# M633X.net
KiCad netlist of a schematic drawn in EAGLE
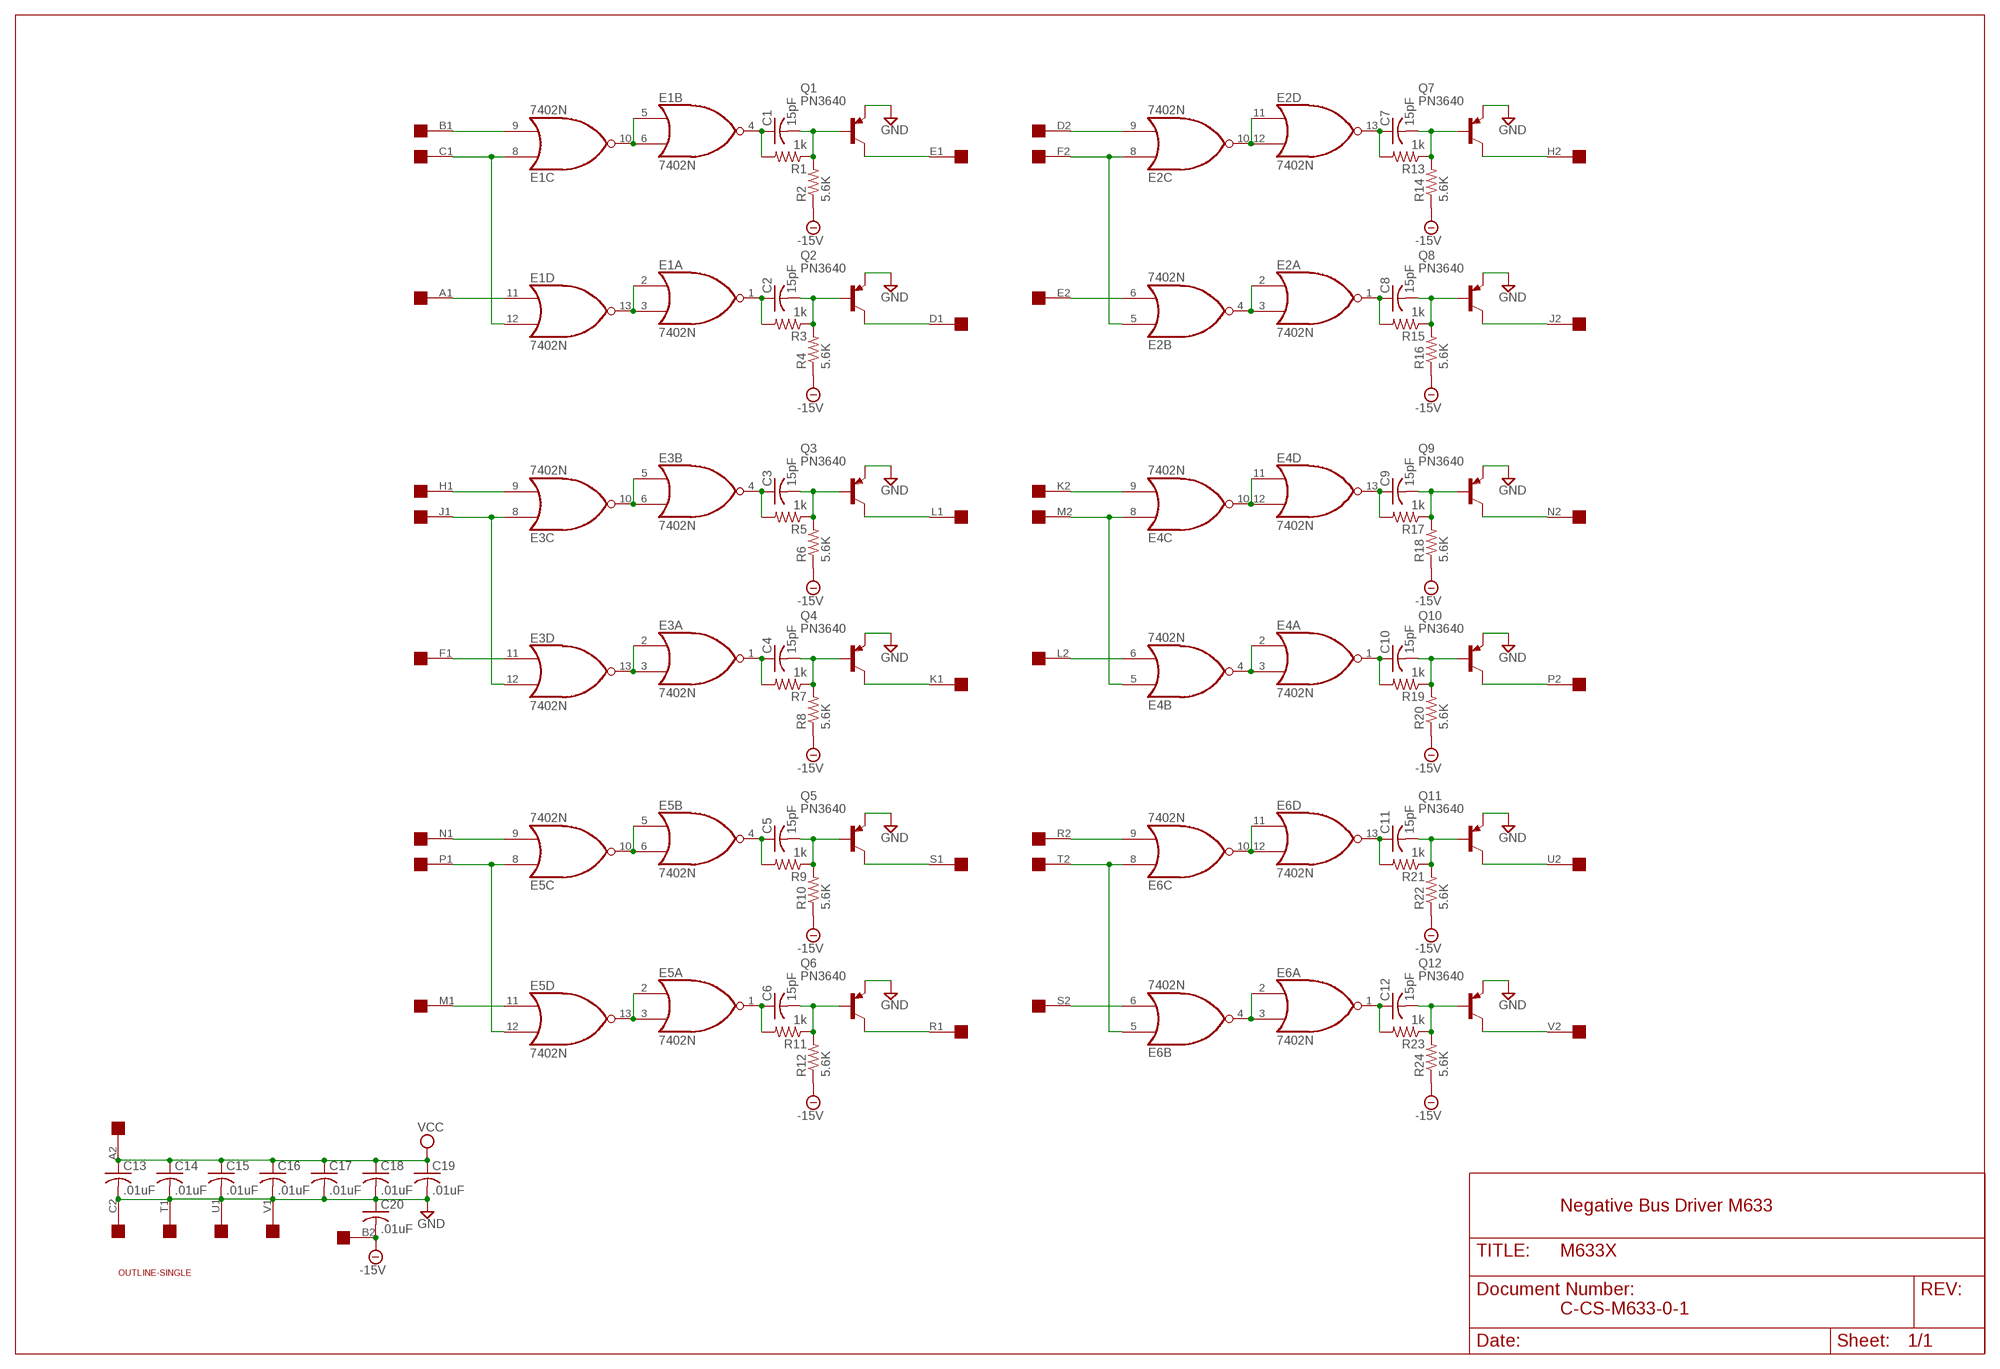
[diagram p0: schematic, sheet 1]

(export (version "E")
  (design (tool "Eeschema 10.0.6"))
  (components
    (comp (ref "C1")
      (value "15pF")
      (footprint "eagle-import:C050-025X075")
      (libsource (lib "eagle-import") (part "C-US050-025X075"))
    )
    (comp (ref "C2")
      (value "15pF")
      (footprint "eagle-import:C050-025X075")
      (libsource (lib "eagle-import") (part "C-US050-025X075"))
    )
    (comp (ref "C3")
      (value "15pF")
      (footprint "eagle-import:C050-025X075")
      (libsource (lib "eagle-import") (part "C-US050-025X075"))
    )
    (comp (ref "C4")
      (value "15pF")
      (footprint "eagle-import:C050-025X075")
      (libsource (lib "eagle-import") (part "C-US050-025X075"))
    )
    (comp (ref "C5")
      (value "15pF")
      (footprint "eagle-import:C050-025X075")
      (libsource (lib "eagle-import") (part "C-US050-025X075"))
    )
    (comp (ref "C6")
      (value "15pF")
      (footprint "eagle-import:C050-025X075")
      (libsource (lib "eagle-import") (part "C-US050-025X075"))
    )
    (comp (ref "C7")
      (value "15pF")
      (footprint "eagle-import:C050-025X075")
      (libsource (lib "eagle-import") (part "C-US050-025X075"))
    )
    (comp (ref "C8")
      (value "15pF")
      (footprint "eagle-import:C050-025X075")
      (libsource (lib "eagle-import") (part "C-US050-025X075"))
    )
    (comp (ref "C9")
      (value "15pF")
      (footprint "eagle-import:C050-025X075")
      (libsource (lib "eagle-import") (part "C-US050-025X075"))
    )
    (comp (ref "C10")
      (value "15pF")
      (footprint "eagle-import:C050-025X075")
      (libsource (lib "eagle-import") (part "C-US050-025X075"))
    )
    (comp (ref "C11")
      (value "15pF")
      (footprint "eagle-import:C050-025X075")
      (libsource (lib "eagle-import") (part "C-US050-025X075"))
    )
    (comp (ref "C12")
      (value "15pF")
      (footprint "eagle-import:C050-025X075")
      (libsource (lib "eagle-import") (part "C-US050-025X075"))
    )
    (comp (ref "C13")
      (value ".01uF")
      (footprint "eagle-import:C050-025X075")
      (libsource (lib "eagle-import") (part "C-US050-025X075"))
    )
    (comp (ref "C14")
      (value ".01uF")
      (footprint "eagle-import:C050-025X075")
      (libsource (lib "eagle-import") (part "C-US050-025X075"))
    )
    (comp (ref "C15")
      (value ".01uF")
      (footprint "eagle-import:C050-025X075")
      (libsource (lib "eagle-import") (part "C-US050-025X075"))
    )
    (comp (ref "C16")
      (value ".01uF")
      (footprint "eagle-import:C050-025X075")
      (libsource (lib "eagle-import") (part "C-US050-025X075"))
    )
    (comp (ref "C17")
      (value ".01uF")
      (footprint "eagle-import:C050-025X075")
      (libsource (lib "eagle-import") (part "C-US050-025X075"))
    )
    (comp (ref "C18")
      (value ".01uF")
      (footprint "eagle-import:C050-025X075")
      (libsource (lib "eagle-import") (part "C-US050-025X075"))
    )
    (comp (ref "C19")
      (value ".01uF")
      (footprint "eagle-import:C050-025X075")
      (libsource (lib "eagle-import") (part "C-US050-025X075"))
    )
    (comp (ref "C20")
      (value ".01uF")
      (footprint "eagle-import:C050-025X075")
      (libsource (lib "eagle-import") (part "C-US050-025X075"))
    )
    (comp (ref "E1")
      (value "7402N")
      (footprint "eagle-import:DIL14")
      (libsource (lib "eagle-import") (part "7402N"))
    )
    (comp (ref "E2")
      (value "7402N")
      (footprint "eagle-import:DIL14")
      (libsource (lib "eagle-import") (part "7402N"))
    )
    (comp (ref "E3")
      (value "7402N")
      (footprint "eagle-import:DIL14")
      (libsource (lib "eagle-import") (part "7402N"))
    )
    (comp (ref "E4")
      (value "7402N")
      (footprint "eagle-import:DIL14")
      (libsource (lib "eagle-import") (part "7402N"))
    )
    (comp (ref "E5")
      (value "7402N")
      (footprint "eagle-import:DIL14")
      (libsource (lib "eagle-import") (part "7402N"))
    )
    (comp (ref "E6")
      (value "7402N")
      (footprint "eagle-import:DIL14")
      (libsource (lib "eagle-import") (part "7402N"))
    )
    (comp (ref "Q1")
      (value "PN3640")
      (footprint "eagle-import:TO39")
      (libsource (lib "eagle-import") (part "2N5415"))
    )
    (comp (ref "Q2")
      (value "PN3640")
      (footprint "eagle-import:TO39")
      (libsource (lib "eagle-import") (part "2N5415"))
    )
    (comp (ref "Q3")
      (value "PN3640")
      (footprint "eagle-import:TO39")
      (libsource (lib "eagle-import") (part "2N5415"))
    )
    (comp (ref "Q4")
      (value "PN3640")
      (footprint "eagle-import:TO39")
      (libsource (lib "eagle-import") (part "2N5415"))
    )
    (comp (ref "Q5")
      (value "PN3640")
      (footprint "eagle-import:TO39")
      (libsource (lib "eagle-import") (part "2N5415"))
    )
    (comp (ref "Q6")
      (value "PN3640")
      (footprint "eagle-import:TO39")
      (libsource (lib "eagle-import") (part "2N5415"))
    )
    (comp (ref "Q7")
      (value "PN3640")
      (footprint "eagle-import:TO39")
      (libsource (lib "eagle-import") (part "2N5415"))
    )
    (comp (ref "Q8")
      (value "PN3640")
      (footprint "eagle-import:TO39")
      (libsource (lib "eagle-import") (part "2N5415"))
    )
    (comp (ref "Q9")
      (value "PN3640")
      (footprint "eagle-import:TO39")
      (libsource (lib "eagle-import") (part "2N5415"))
    )
    (comp (ref "Q10")
      (value "PN3640")
      (footprint "eagle-import:TO39")
      (libsource (lib "eagle-import") (part "2N5415"))
    )
    (comp (ref "Q11")
      (value "PN3640")
      (footprint "eagle-import:TO39")
      (libsource (lib "eagle-import") (part "2N5415"))
    )
    (comp (ref "Q12")
      (value "PN3640")
      (footprint "eagle-import:TO39")
      (libsource (lib "eagle-import") (part "2N5415"))
    )
    (comp (ref "R1")
      (value "1k")
      (footprint "eagle-import:0207_10")
      (libsource (lib "eagle-import") (part "R-US_0207/10"))
    )
    (comp (ref "R2")
      (value "5.6K")
      (footprint "eagle-import:0207_10")
      (libsource (lib "eagle-import") (part "R-US_0207/10"))
    )
    (comp (ref "R3")
      (value "1k")
      (footprint "eagle-import:0207_10")
      (libsource (lib "eagle-import") (part "R-US_0207/10"))
    )
    (comp (ref "R4")
      (value "5.6K")
      (footprint "eagle-import:0207_10")
      (libsource (lib "eagle-import") (part "R-US_0207/10"))
    )
    (comp (ref "R5")
      (value "1k")
      (footprint "eagle-import:0207_10")
      (libsource (lib "eagle-import") (part "R-US_0207/10"))
    )
    (comp (ref "R6")
      (value "5.6K")
      (footprint "eagle-import:0207_10")
      (libsource (lib "eagle-import") (part "R-US_0207/10"))
    )
    (comp (ref "R7")
      (value "1k")
      (footprint "eagle-import:0207_10")
      (libsource (lib "eagle-import") (part "R-US_0207/10"))
    )
    (comp (ref "R8")
      (value "5.6K")
      (footprint "eagle-import:0207_10")
      (libsource (lib "eagle-import") (part "R-US_0207/10"))
    )
    (comp (ref "R9")
      (value "1k")
      (footprint "eagle-import:0207_10")
      (libsource (lib "eagle-import") (part "R-US_0207/10"))
    )
    (comp (ref "R10")
      (value "5.6K")
      (footprint "eagle-import:0207_10")
      (libsource (lib "eagle-import") (part "R-US_0207/10"))
    )
    (comp (ref "R11")
      (value "1k")
      (footprint "eagle-import:0207_10")
      (libsource (lib "eagle-import") (part "R-US_0207/10"))
    )
    (comp (ref "R12")
      (value "5.6K")
      (footprint "eagle-import:0207_10")
      (libsource (lib "eagle-import") (part "R-US_0207/10"))
    )
    (comp (ref "R13")
      (value "1k")
      (footprint "eagle-import:0207_10")
      (libsource (lib "eagle-import") (part "R-US_0207/10"))
    )
    (comp (ref "R14")
      (value "5.6K")
      (footprint "eagle-import:0207_10")
      (libsource (lib "eagle-import") (part "R-US_0207/10"))
    )
    (comp (ref "R15")
      (value "1k")
      (footprint "eagle-import:0207_10")
      (libsource (lib "eagle-import") (part "R-US_0207/10"))
    )
    (comp (ref "R16")
      (value "5.6K")
      (footprint "eagle-import:0207_10")
      (libsource (lib "eagle-import") (part "R-US_0207/10"))
    )
    (comp (ref "R17")
      (value "1k")
      (footprint "eagle-import:0207_10")
      (libsource (lib "eagle-import") (part "R-US_0207/10"))
    )
    (comp (ref "R18")
      (value "5.6K")
      (footprint "eagle-import:0207_10")
      (libsource (lib "eagle-import") (part "R-US_0207/10"))
    )
    (comp (ref "R19")
      (value "1k")
      (footprint "eagle-import:0207_10")
      (libsource (lib "eagle-import") (part "R-US_0207/10"))
    )
    (comp (ref "R20")
      (value "5.6K")
      (footprint "eagle-import:0207_10")
      (libsource (lib "eagle-import") (part "R-US_0207/10"))
    )
    (comp (ref "R21")
      (value "1k")
      (footprint "eagle-import:0207_10")
      (libsource (lib "eagle-import") (part "R-US_0207/10"))
    )
    (comp (ref "R22")
      (value "5.6K")
      (footprint "eagle-import:0207_10")
      (libsource (lib "eagle-import") (part "R-US_0207/10"))
    )
    (comp (ref "R23")
      (value "1k")
      (footprint "eagle-import:0207_10")
      (libsource (lib "eagle-import") (part "R-US_0207/10"))
    )
    (comp (ref "R24")
      (value "5.6K")
      (footprint "eagle-import:0207_10")
      (libsource (lib "eagle-import") (part "R-US_0207/10"))
    )
    (comp (ref "U$1")
      (value "OUTLINE-SINGLE")
      (footprint "eagle-import:SINGLE")
      (libsource (lib "eagle-import") (part "OUTLINE-SINGLE"))
    )
    (comp (ref "U$4")
      (value "SINGLE")
      (footprint "eagle-import:EDGE-CON2")
      (libsource (lib "eagle-import") (part "SINGLE"))
    )
  )
  (nets
    (net (code "1") (name "-15V") (class "Default")
      (node (ref "C20") (pin "2") (pinfunction "2_2") (pintype "passive"))
      (node (ref "R10") (pin "1") (pinfunction "1_1") (pintype "passive"))
      (node (ref "R12") (pin "1") (pinfunction "1_1") (pintype "passive"))
      (node (ref "R14") (pin "1") (pinfunction "1_1") (pintype "passive"))
      (node (ref "R16") (pin "1") (pinfunction "1_1") (pintype "passive"))
      (node (ref "R18") (pin "1") (pinfunction "1_1") (pintype "passive"))
      (node (ref "R2") (pin "1") (pinfunction "1_1") (pintype "passive"))
      (node (ref "R20") (pin "1") (pinfunction "1_1") (pintype "passive"))
      (node (ref "R22") (pin "1") (pinfunction "1_1") (pintype "passive"))
      (node (ref "R24") (pin "1") (pinfunction "1_1") (pintype "passive"))
      (node (ref "R4") (pin "1") (pinfunction "1_1") (pintype "passive"))
      (node (ref "R6") (pin "1") (pinfunction "1_1") (pintype "passive"))
      (node (ref "R8") (pin "1") (pinfunction "1_1") (pintype "passive"))
      (node (ref "U$4") (pin "B2") (pinfunction "1_B2") (pintype "bidirectional"))
    )
    (net (code "2") (name "GND") (class "Default")
      (node (ref "C13") (pin "2") (pinfunction "2_2") (pintype "passive"))
      (node (ref "C14") (pin "2") (pinfunction "2_2") (pintype "passive"))
      (node (ref "C15") (pin "2") (pinfunction "2_2") (pintype "passive"))
      (node (ref "C16") (pin "2") (pinfunction "2_2") (pintype "passive"))
      (node (ref "C17") (pin "2") (pinfunction "2_2") (pintype "passive"))
      (node (ref "C18") (pin "2") (pinfunction "2_2") (pintype "passive"))
      (node (ref "C19") (pin "2") (pinfunction "2_2") (pintype "passive"))
      (node (ref "C20") (pin "1") (pinfunction "1_1") (pintype "passive"))
      (node (ref "Q1") (pin "1") (pinfunction "E_1") (pintype "passive"))
      (node (ref "Q10") (pin "1") (pinfunction "E_1") (pintype "passive"))
      (node (ref "Q11") (pin "1") (pinfunction "E_1") (pintype "passive"))
      (node (ref "Q12") (pin "1") (pinfunction "E_1") (pintype "passive"))
      (node (ref "Q2") (pin "1") (pinfunction "E_1") (pintype "passive"))
      (node (ref "Q3") (pin "1") (pinfunction "E_1") (pintype "passive"))
      (node (ref "Q4") (pin "1") (pinfunction "E_1") (pintype "passive"))
      (node (ref "Q5") (pin "1") (pinfunction "E_1") (pintype "passive"))
      (node (ref "Q6") (pin "1") (pinfunction "E_1") (pintype "passive"))
      (node (ref "Q7") (pin "1") (pinfunction "E_1") (pintype "passive"))
      (node (ref "Q8") (pin "1") (pinfunction "E_1") (pintype "passive"))
      (node (ref "Q9") (pin "1") (pinfunction "E_1") (pintype "passive"))
      (node (ref "U$4") (pin "C2") (pinfunction "1_C2") (pintype "bidirectional"))
      (node (ref "U$4") (pin "T1") (pinfunction "1_T1") (pintype "bidirectional"))
      (node (ref "U$4") (pin "U1") (pinfunction "1_U1") (pintype "bidirectional"))
      (node (ref "U$4") (pin "V1") (pinfunction "1_V1") (pintype "bidirectional"))
    )
    (net (code "3") (name "Net-(E1A-I0)") (class "Default")
      (node (ref "E1") (pin "13") (pinfunction "O_13") (pintype "output"))
      (node (ref "E1") (pin "2") (pinfunction "I0_2") (pintype "input"))
      (node (ref "E1") (pin "3") (pinfunction "I1_3") (pintype "input"))
    )
    (net (code "4") (name "Net-(E1A-O)") (class "Default")
      (node (ref "C2") (pin "1") (pinfunction "1_1") (pintype "passive"))
      (node (ref "E1") (pin "1") (pinfunction "O_1") (pintype "output"))
      (node (ref "R3") (pin "2") (pinfunction "2_2") (pintype "passive"))
    )
    (net (code "5") (name "Net-(E1B-I0)") (class "Default")
      (node (ref "E1") (pin "10") (pinfunction "O_10") (pintype "output"))
      (node (ref "E1") (pin "5") (pinfunction "I0_5") (pintype "input"))
      (node (ref "E1") (pin "6") (pinfunction "I1_6") (pintype "input"))
    )
    (net (code "6") (name "Net-(E1B-O)") (class "Default")
      (node (ref "C1") (pin "1") (pinfunction "1_1") (pintype "passive"))
      (node (ref "E1") (pin "4") (pinfunction "O_4") (pintype "output"))
      (node (ref "R1") (pin "2") (pinfunction "2_2") (pintype "passive"))
    )
    (net (code "7") (name "Net-(E1C-I0)") (class "Default")
      (node (ref "E1") (pin "12") (pinfunction "I1_12") (pintype "input"))
      (node (ref "E1") (pin "8") (pinfunction "I0_8") (pintype "input"))
      (node (ref "U$4") (pin "C1") (pinfunction "1_C1") (pintype "bidirectional"))
    )
    (net (code "8") (name "Net-(E1C-I1)") (class "Default")
      (node (ref "E1") (pin "9") (pinfunction "I1_9") (pintype "input"))
      (node (ref "U$4") (pin "B1") (pinfunction "1_B1") (pintype "bidirectional"))
    )
    (net (code "9") (name "Net-(E1D-I0)") (class "Default")
      (node (ref "E1") (pin "11") (pinfunction "I0_11") (pintype "input"))
      (node (ref "U$4") (pin "A1") (pinfunction "1_A1") (pintype "bidirectional"))
    )
    (net (code "10") (name "Net-(E2A-I0)") (class "Default")
      (node (ref "E2") (pin "2") (pinfunction "I0_2") (pintype "input"))
      (node (ref "E2") (pin "3") (pinfunction "I1_3") (pintype "input"))
      (node (ref "E2") (pin "4") (pinfunction "O_4") (pintype "output"))
    )
    (net (code "11") (name "Net-(E2A-O)") (class "Default")
      (node (ref "C8") (pin "1") (pinfunction "1_1") (pintype "passive"))
      (node (ref "E2") (pin "1") (pinfunction "O_1") (pintype "output"))
      (node (ref "R15") (pin "2") (pinfunction "2_2") (pintype "passive"))
    )
    (net (code "12") (name "Net-(E2B-I0)") (class "Default")
      (node (ref "E2") (pin "5") (pinfunction "I0_5") (pintype "input"))
      (node (ref "E2") (pin "8") (pinfunction "I0_8") (pintype "input"))
      (node (ref "U$4") (pin "F2") (pinfunction "1_F2") (pintype "bidirectional"))
    )
    (net (code "13") (name "Net-(E2B-I1)") (class "Default")
      (node (ref "E2") (pin "6") (pinfunction "I1_6") (pintype "input"))
      (node (ref "U$4") (pin "E2") (pinfunction "1_E2") (pintype "bidirectional"))
    )
    (net (code "14") (name "Net-(E2C-I1)") (class "Default")
      (node (ref "E2") (pin "9") (pinfunction "I1_9") (pintype "input"))
      (node (ref "U$4") (pin "D2") (pinfunction "1_D2") (pintype "bidirectional"))
    )
    (net (code "15") (name "Net-(E2C-O)") (class "Default")
      (node (ref "E2") (pin "10") (pinfunction "O_10") (pintype "output"))
      (node (ref "E2") (pin "11") (pinfunction "I0_11") (pintype "input"))
      (node (ref "E2") (pin "12") (pinfunction "I1_12") (pintype "input"))
    )
    (net (code "16") (name "Net-(E2D-O)") (class "Default")
      (node (ref "C7") (pin "1") (pinfunction "1_1") (pintype "passive"))
      (node (ref "E2") (pin "13") (pinfunction "O_13") (pintype "output"))
      (node (ref "R13") (pin "2") (pinfunction "2_2") (pintype "passive"))
    )
    (net (code "17") (name "Net-(E3A-I0)") (class "Default")
      (node (ref "E3") (pin "13") (pinfunction "O_13") (pintype "output"))
      (node (ref "E3") (pin "2") (pinfunction "I0_2") (pintype "input"))
      (node (ref "E3") (pin "3") (pinfunction "I1_3") (pintype "input"))
    )
    (net (code "18") (name "Net-(E3A-O)") (class "Default")
      (node (ref "C4") (pin "1") (pinfunction "1_1") (pintype "passive"))
      (node (ref "E3") (pin "1") (pinfunction "O_1") (pintype "output"))
      (node (ref "R7") (pin "2") (pinfunction "2_2") (pintype "passive"))
    )
    (net (code "19") (name "Net-(E3B-I0)") (class "Default")
      (node (ref "E3") (pin "10") (pinfunction "O_10") (pintype "output"))
      (node (ref "E3") (pin "5") (pinfunction "I0_5") (pintype "input"))
      (node (ref "E3") (pin "6") (pinfunction "I1_6") (pintype "input"))
    )
    (net (code "20") (name "Net-(E3B-O)") (class "Default")
      (node (ref "C3") (pin "1") (pinfunction "1_1") (pintype "passive"))
      (node (ref "E3") (pin "4") (pinfunction "O_4") (pintype "output"))
      (node (ref "R5") (pin "2") (pinfunction "2_2") (pintype "passive"))
    )
    (net (code "21") (name "Net-(E3C-I0)") (class "Default")
      (node (ref "E3") (pin "12") (pinfunction "I1_12") (pintype "input"))
      (node (ref "E3") (pin "8") (pinfunction "I0_8") (pintype "input"))
      (node (ref "U$4") (pin "J1") (pinfunction "1_J1") (pintype "bidirectional"))
    )
    (net (code "22") (name "Net-(E3C-I1)") (class "Default")
      (node (ref "E3") (pin "9") (pinfunction "I1_9") (pintype "input"))
      (node (ref "U$4") (pin "H1") (pinfunction "1_H1") (pintype "bidirectional"))
    )
    (net (code "23") (name "Net-(E3D-I0)") (class "Default")
      (node (ref "E3") (pin "11") (pinfunction "I0_11") (pintype "input"))
      (node (ref "U$4") (pin "F1") (pinfunction "1_F1") (pintype "bidirectional"))
    )
    (net (code "24") (name "Net-(E4A-I0)") (class "Default")
      (node (ref "E4") (pin "2") (pinfunction "I0_2") (pintype "input"))
      (node (ref "E4") (pin "3") (pinfunction "I1_3") (pintype "input"))
      (node (ref "E4") (pin "4") (pinfunction "O_4") (pintype "output"))
    )
    (net (code "25") (name "Net-(E4A-O)") (class "Default")
      (node (ref "C10") (pin "1") (pinfunction "1_1") (pintype "passive"))
      (node (ref "E4") (pin "1") (pinfunction "O_1") (pintype "output"))
      (node (ref "R19") (pin "2") (pinfunction "2_2") (pintype "passive"))
    )
    (net (code "26") (name "Net-(E4B-I0)") (class "Default")
      (node (ref "E4") (pin "5") (pinfunction "I0_5") (pintype "input"))
      (node (ref "E4") (pin "8") (pinfunction "I0_8") (pintype "input"))
      (node (ref "U$4") (pin "M2") (pinfunction "1_M2") (pintype "bidirectional"))
    )
    (net (code "27") (name "Net-(E4B-I1)") (class "Default")
      (node (ref "E4") (pin "6") (pinfunction "I1_6") (pintype "input"))
      (node (ref "U$4") (pin "L2") (pinfunction "1_L2") (pintype "bidirectional"))
    )
    (net (code "28") (name "Net-(E4C-I1)") (class "Default")
      (node (ref "E4") (pin "9") (pinfunction "I1_9") (pintype "input"))
      (node (ref "U$4") (pin "K2") (pinfunction "1_K2") (pintype "bidirectional"))
    )
    (net (code "29") (name "Net-(E4C-O)") (class "Default")
      (node (ref "E4") (pin "10") (pinfunction "O_10") (pintype "output"))
      (node (ref "E4") (pin "11") (pinfunction "I0_11") (pintype "input"))
      (node (ref "E4") (pin "12") (pinfunction "I1_12") (pintype "input"))
    )
    (net (code "30") (name "Net-(E4D-O)") (class "Default")
      (node (ref "C9") (pin "1") (pinfunction "1_1") (pintype "passive"))
      (node (ref "E4") (pin "13") (pinfunction "O_13") (pintype "output"))
      (node (ref "R17") (pin "2") (pinfunction "2_2") (pintype "passive"))
    )
    (net (code "31") (name "Net-(E5A-I0)") (class "Default")
      (node (ref "E5") (pin "13") (pinfunction "O_13") (pintype "output"))
      (node (ref "E5") (pin "2") (pinfunction "I0_2") (pintype "input"))
      (node (ref "E5") (pin "3") (pinfunction "I1_3") (pintype "input"))
    )
    (net (code "32") (name "Net-(E5A-O)") (class "Default")
      (node (ref "C6") (pin "1") (pinfunction "1_1") (pintype "passive"))
      (node (ref "E5") (pin "1") (pinfunction "O_1") (pintype "output"))
      (node (ref "R11") (pin "2") (pinfunction "2_2") (pintype "passive"))
    )
    (net (code "33") (name "Net-(E5B-I0)") (class "Default")
      (node (ref "E5") (pin "10") (pinfunction "O_10") (pintype "output"))
      (node (ref "E5") (pin "5") (pinfunction "I0_5") (pintype "input"))
      (node (ref "E5") (pin "6") (pinfunction "I1_6") (pintype "input"))
    )
    (net (code "34") (name "Net-(E5B-O)") (class "Default")
      (node (ref "C5") (pin "1") (pinfunction "1_1") (pintype "passive"))
      (node (ref "E5") (pin "4") (pinfunction "O_4") (pintype "output"))
      (node (ref "R9") (pin "2") (pinfunction "2_2") (pintype "passive"))
    )
    (net (code "35") (name "Net-(E5C-I0)") (class "Default")
      (node (ref "E5") (pin "12") (pinfunction "I1_12") (pintype "input"))
      (node (ref "E5") (pin "8") (pinfunction "I0_8") (pintype "input"))
      (node (ref "U$4") (pin "P1") (pinfunction "1_P1") (pintype "bidirectional"))
    )
    (net (code "36") (name "Net-(E5C-I1)") (class "Default")
      (node (ref "E5") (pin "9") (pinfunction "I1_9") (pintype "input"))
      (node (ref "U$4") (pin "N1") (pinfunction "1_N1") (pintype "bidirectional"))
    )
    (net (code "37") (name "Net-(E5D-I0)") (class "Default")
      (node (ref "E5") (pin "11") (pinfunction "I0_11") (pintype "input"))
      (node (ref "U$4") (pin "M1") (pinfunction "1_M1") (pintype "bidirectional"))
    )
    (net (code "38") (name "Net-(E6A-I0)") (class "Default")
      (node (ref "E6") (pin "2") (pinfunction "I0_2") (pintype "input"))
      (node (ref "E6") (pin "3") (pinfunction "I1_3") (pintype "input"))
      (node (ref "E6") (pin "4") (pinfunction "O_4") (pintype "output"))
    )
    (net (code "39") (name "Net-(E6A-O)") (class "Default")
      (node (ref "C12") (pin "1") (pinfunction "1_1") (pintype "passive"))
      (node (ref "E6") (pin "1") (pinfunction "O_1") (pintype "output"))
      (node (ref "R23") (pin "2") (pinfunction "2_2") (pintype "passive"))
    )
    (net (code "40") (name "Net-(E6B-I0)") (class "Default")
      (node (ref "E6") (pin "5") (pinfunction "I0_5") (pintype "input"))
      (node (ref "E6") (pin "8") (pinfunction "I0_8") (pintype "input"))
      (node (ref "U$4") (pin "T2") (pinfunction "1_T2") (pintype "bidirectional"))
    )
    (net (code "41") (name "Net-(E6B-I1)") (class "Default")
      (node (ref "E6") (pin "6") (pinfunction "I1_6") (pintype "input"))
      (node (ref "U$4") (pin "S2") (pinfunction "1_S2") (pintype "bidirectional"))
    )
    (net (code "42") (name "Net-(E6C-I1)") (class "Default")
      (node (ref "E6") (pin "9") (pinfunction "I1_9") (pintype "input"))
      (node (ref "U$4") (pin "R2") (pinfunction "1_R2") (pintype "bidirectional"))
    )
    (net (code "43") (name "Net-(E6C-O)") (class "Default")
      (node (ref "E6") (pin "10") (pinfunction "O_10") (pintype "output"))
      (node (ref "E6") (pin "11") (pinfunction "I0_11") (pintype "input"))
      (node (ref "E6") (pin "12") (pinfunction "I1_12") (pintype "input"))
    )
    (net (code "44") (name "Net-(E6D-O)") (class "Default")
      (node (ref "C11") (pin "1") (pinfunction "1_1") (pintype "passive"))
      (node (ref "E6") (pin "13") (pinfunction "O_13") (pintype "output"))
      (node (ref "R21") (pin "2") (pinfunction "2_2") (pintype "passive"))
    )
    (net (code "45") (name "Net-(Q1-B)") (class "Default")
      (node (ref "C1") (pin "2") (pinfunction "2_2") (pintype "passive"))
      (node (ref "Q1") (pin "2") (pinfunction "B_2") (pintype "passive"))
      (node (ref "R1") (pin "1") (pinfunction "1_1") (pintype "passive"))
      (node (ref "R2") (pin "2") (pinfunction "2_2") (pintype "passive"))
    )
    (net (code "46") (name "Net-(Q1-C)") (class "Default")
      (node (ref "Q1") (pin "3") (pinfunction "C_3") (pintype "passive"))
      (node (ref "U$4") (pin "E1") (pinfunction "1_E1") (pintype "bidirectional"))
    )
    (net (code "47") (name "Net-(Q2-B)") (class "Default")
      (node (ref "C2") (pin "2") (pinfunction "2_2") (pintype "passive"))
      (node (ref "Q2") (pin "2") (pinfunction "B_2") (pintype "passive"))
      (node (ref "R3") (pin "1") (pinfunction "1_1") (pintype "passive"))
      (node (ref "R4") (pin "2") (pinfunction "2_2") (pintype "passive"))
    )
    (net (code "48") (name "Net-(Q2-C)") (class "Default")
      (node (ref "Q2") (pin "3") (pinfunction "C_3") (pintype "passive"))
      (node (ref "U$4") (pin "D1") (pinfunction "1_D1") (pintype "bidirectional"))
    )
    (net (code "49") (name "Net-(Q3-B)") (class "Default")
      (node (ref "C3") (pin "2") (pinfunction "2_2") (pintype "passive"))
      (node (ref "Q3") (pin "2") (pinfunction "B_2") (pintype "passive"))
      (node (ref "R5") (pin "1") (pinfunction "1_1") (pintype "passive"))
      (node (ref "R6") (pin "2") (pinfunction "2_2") (pintype "passive"))
    )
    (net (code "50") (name "Net-(Q3-C)") (class "Default")
      (node (ref "Q3") (pin "3") (pinfunction "C_3") (pintype "passive"))
      (node (ref "U$4") (pin "L1") (pinfunction "1_L1") (pintype "bidirectional"))
    )
    (net (code "51") (name "Net-(Q4-B)") (class "Default")
      (node (ref "C4") (pin "2") (pinfunction "2_2") (pintype "passive"))
      (node (ref "Q4") (pin "2") (pinfunction "B_2") (pintype "passive"))
      (node (ref "R7") (pin "1") (pinfunction "1_1") (pintype "passive"))
      (node (ref "R8") (pin "2") (pinfunction "2_2") (pintype "passive"))
    )
    (net (code "52") (name "Net-(Q4-C)") (class "Default")
      (node (ref "Q4") (pin "3") (pinfunction "C_3") (pintype "passive"))
      (node (ref "U$4") (pin "K1") (pinfunction "1_K1") (pintype "bidirectional"))
    )
    (net (code "53") (name "Net-(Q5-B)") (class "Default")
      (node (ref "C5") (pin "2") (pinfunction "2_2") (pintype "passive"))
      (node (ref "Q5") (pin "2") (pinfunction "B_2") (pintype "passive"))
      (node (ref "R10") (pin "2") (pinfunction "2_2") (pintype "passive"))
      (node (ref "R9") (pin "1") (pinfunction "1_1") (pintype "passive"))
    )
    (net (code "54") (name "Net-(Q5-C)") (class "Default")
      (node (ref "Q5") (pin "3") (pinfunction "C_3") (pintype "passive"))
      (node (ref "U$4") (pin "S1") (pinfunction "1_S1") (pintype "bidirectional"))
    )
    (net (code "55") (name "Net-(Q6-B)") (class "Default")
      (node (ref "C6") (pin "2") (pinfunction "2_2") (pintype "passive"))
      (node (ref "Q6") (pin "2") (pinfunction "B_2") (pintype "passive"))
      (node (ref "R11") (pin "1") (pinfunction "1_1") (pintype "passive"))
      (node (ref "R12") (pin "2") (pinfunction "2_2") (pintype "passive"))
    )
    (net (code "56") (name "Net-(Q6-C)") (class "Default")
      (node (ref "Q6") (pin "3") (pinfunction "C_3") (pintype "passive"))
      (node (ref "U$4") (pin "R1") (pinfunction "1_R1") (pintype "bidirectional"))
    )
    (net (code "57") (name "Net-(Q7-B)") (class "Default")
      (node (ref "C7") (pin "2") (pinfunction "2_2") (pintype "passive"))
      (node (ref "Q7") (pin "2") (pinfunction "B_2") (pintype "passive"))
      (node (ref "R13") (pin "1") (pinfunction "1_1") (pintype "passive"))
      (node (ref "R14") (pin "2") (pinfunction "2_2") (pintype "passive"))
    )
    (net (code "58") (name "Net-(Q7-C)") (class "Default")
      (node (ref "Q7") (pin "3") (pinfunction "C_3") (pintype "passive"))
      (node (ref "U$4") (pin "H2") (pinfunction "1_H2") (pintype "bidirectional"))
    )
    (net (code "59") (name "Net-(Q8-B)") (class "Default")
      (node (ref "C8") (pin "2") (pinfunction "2_2") (pintype "passive"))
      (node (ref "Q8") (pin "2") (pinfunction "B_2") (pintype "passive"))
      (node (ref "R15") (pin "1") (pinfunction "1_1") (pintype "passive"))
      (node (ref "R16") (pin "2") (pinfunction "2_2") (pintype "passive"))
    )
    (net (code "60") (name "Net-(Q8-C)") (class "Default")
      (node (ref "Q8") (pin "3") (pinfunction "C_3") (pintype "passive"))
      (node (ref "U$4") (pin "J2") (pinfunction "1_J2") (pintype "bidirectional"))
    )
    (net (code "61") (name "Net-(Q9-B)") (class "Default")
      (node (ref "C9") (pin "2") (pinfunction "2_2") (pintype "passive"))
      (node (ref "Q9") (pin "2") (pinfunction "B_2") (pintype "passive"))
      (node (ref "R17") (pin "1") (pinfunction "1_1") (pintype "passive"))
      (node (ref "R18") (pin "2") (pinfunction "2_2") (pintype "passive"))
    )
    (net (code "62") (name "Net-(Q9-C)") (class "Default")
      (node (ref "Q9") (pin "3") (pinfunction "C_3") (pintype "passive"))
      (node (ref "U$4") (pin "N2") (pinfunction "1_N2") (pintype "bidirectional"))
    )
    (net (code "63") (name "Net-(Q10-B)") (class "Default")
      (node (ref "C10") (pin "2") (pinfunction "2_2") (pintype "passive"))
      (node (ref "Q10") (pin "2") (pinfunction "B_2") (pintype "passive"))
      (node (ref "R19") (pin "1") (pinfunction "1_1") (pintype "passive"))
      (node (ref "R20") (pin "2") (pinfunction "2_2") (pintype "passive"))
    )
    (net (code "64") (name "Net-(Q10-C)") (class "Default")
      (node (ref "Q10") (pin "3") (pinfunction "C_3") (pintype "passive"))
      (node (ref "U$4") (pin "P2") (pinfunction "1_P2") (pintype "bidirectional"))
    )
    (net (code "65") (name "Net-(Q11-B)") (class "Default")
      (node (ref "C11") (pin "2") (pinfunction "2_2") (pintype "passive"))
      (node (ref "Q11") (pin "2") (pinfunction "B_2") (pintype "passive"))
      (node (ref "R21") (pin "1") (pinfunction "1_1") (pintype "passive"))
      (node (ref "R22") (pin "2") (pinfunction "2_2") (pintype "passive"))
    )
    (net (code "66") (name "Net-(Q11-C)") (class "Default")
      (node (ref "Q11") (pin "3") (pinfunction "C_3") (pintype "passive"))
      (node (ref "U$4") (pin "U2") (pinfunction "1_U2") (pintype "bidirectional"))
    )
    (net (code "67") (name "Net-(Q12-B)") (class "Default")
      (node (ref "C12") (pin "2") (pinfunction "2_2") (pintype "passive"))
      (node (ref "Q12") (pin "2") (pinfunction "B_2") (pintype "passive"))
      (node (ref "R23") (pin "1") (pinfunction "1_1") (pintype "passive"))
      (node (ref "R24") (pin "2") (pinfunction "2_2") (pintype "passive"))
    )
    (net (code "68") (name "Net-(Q12-C)") (class "Default")
      (node (ref "Q12") (pin "3") (pinfunction "C_3") (pintype "passive"))
      (node (ref "U$4") (pin "V2") (pinfunction "1_V2") (pintype "bidirectional"))
    )
    (net (code "69") (name "VCC") (class "Default")
      (node (ref "C13") (pin "1") (pinfunction "1_1") (pintype "passive"))
      (node (ref "C14") (pin "1") (pinfunction "1_1") (pintype "passive"))
      (node (ref "C15") (pin "1") (pinfunction "1_1") (pintype "passive"))
      (node (ref "C16") (pin "1") (pinfunction "1_1") (pintype "passive"))
      (node (ref "C17") (pin "1") (pinfunction "1_1") (pintype "passive"))
      (node (ref "C18") (pin "1") (pinfunction "1_1") (pintype "passive"))
      (node (ref "C19") (pin "1") (pinfunction "1_1") (pintype "passive"))
      (node (ref "U$4") (pin "A2") (pinfunction "1_A2") (pintype "bidirectional"))
    )
  )
)
